# Template.net
KiCad netlist of a schematic drawn in Altium Designer
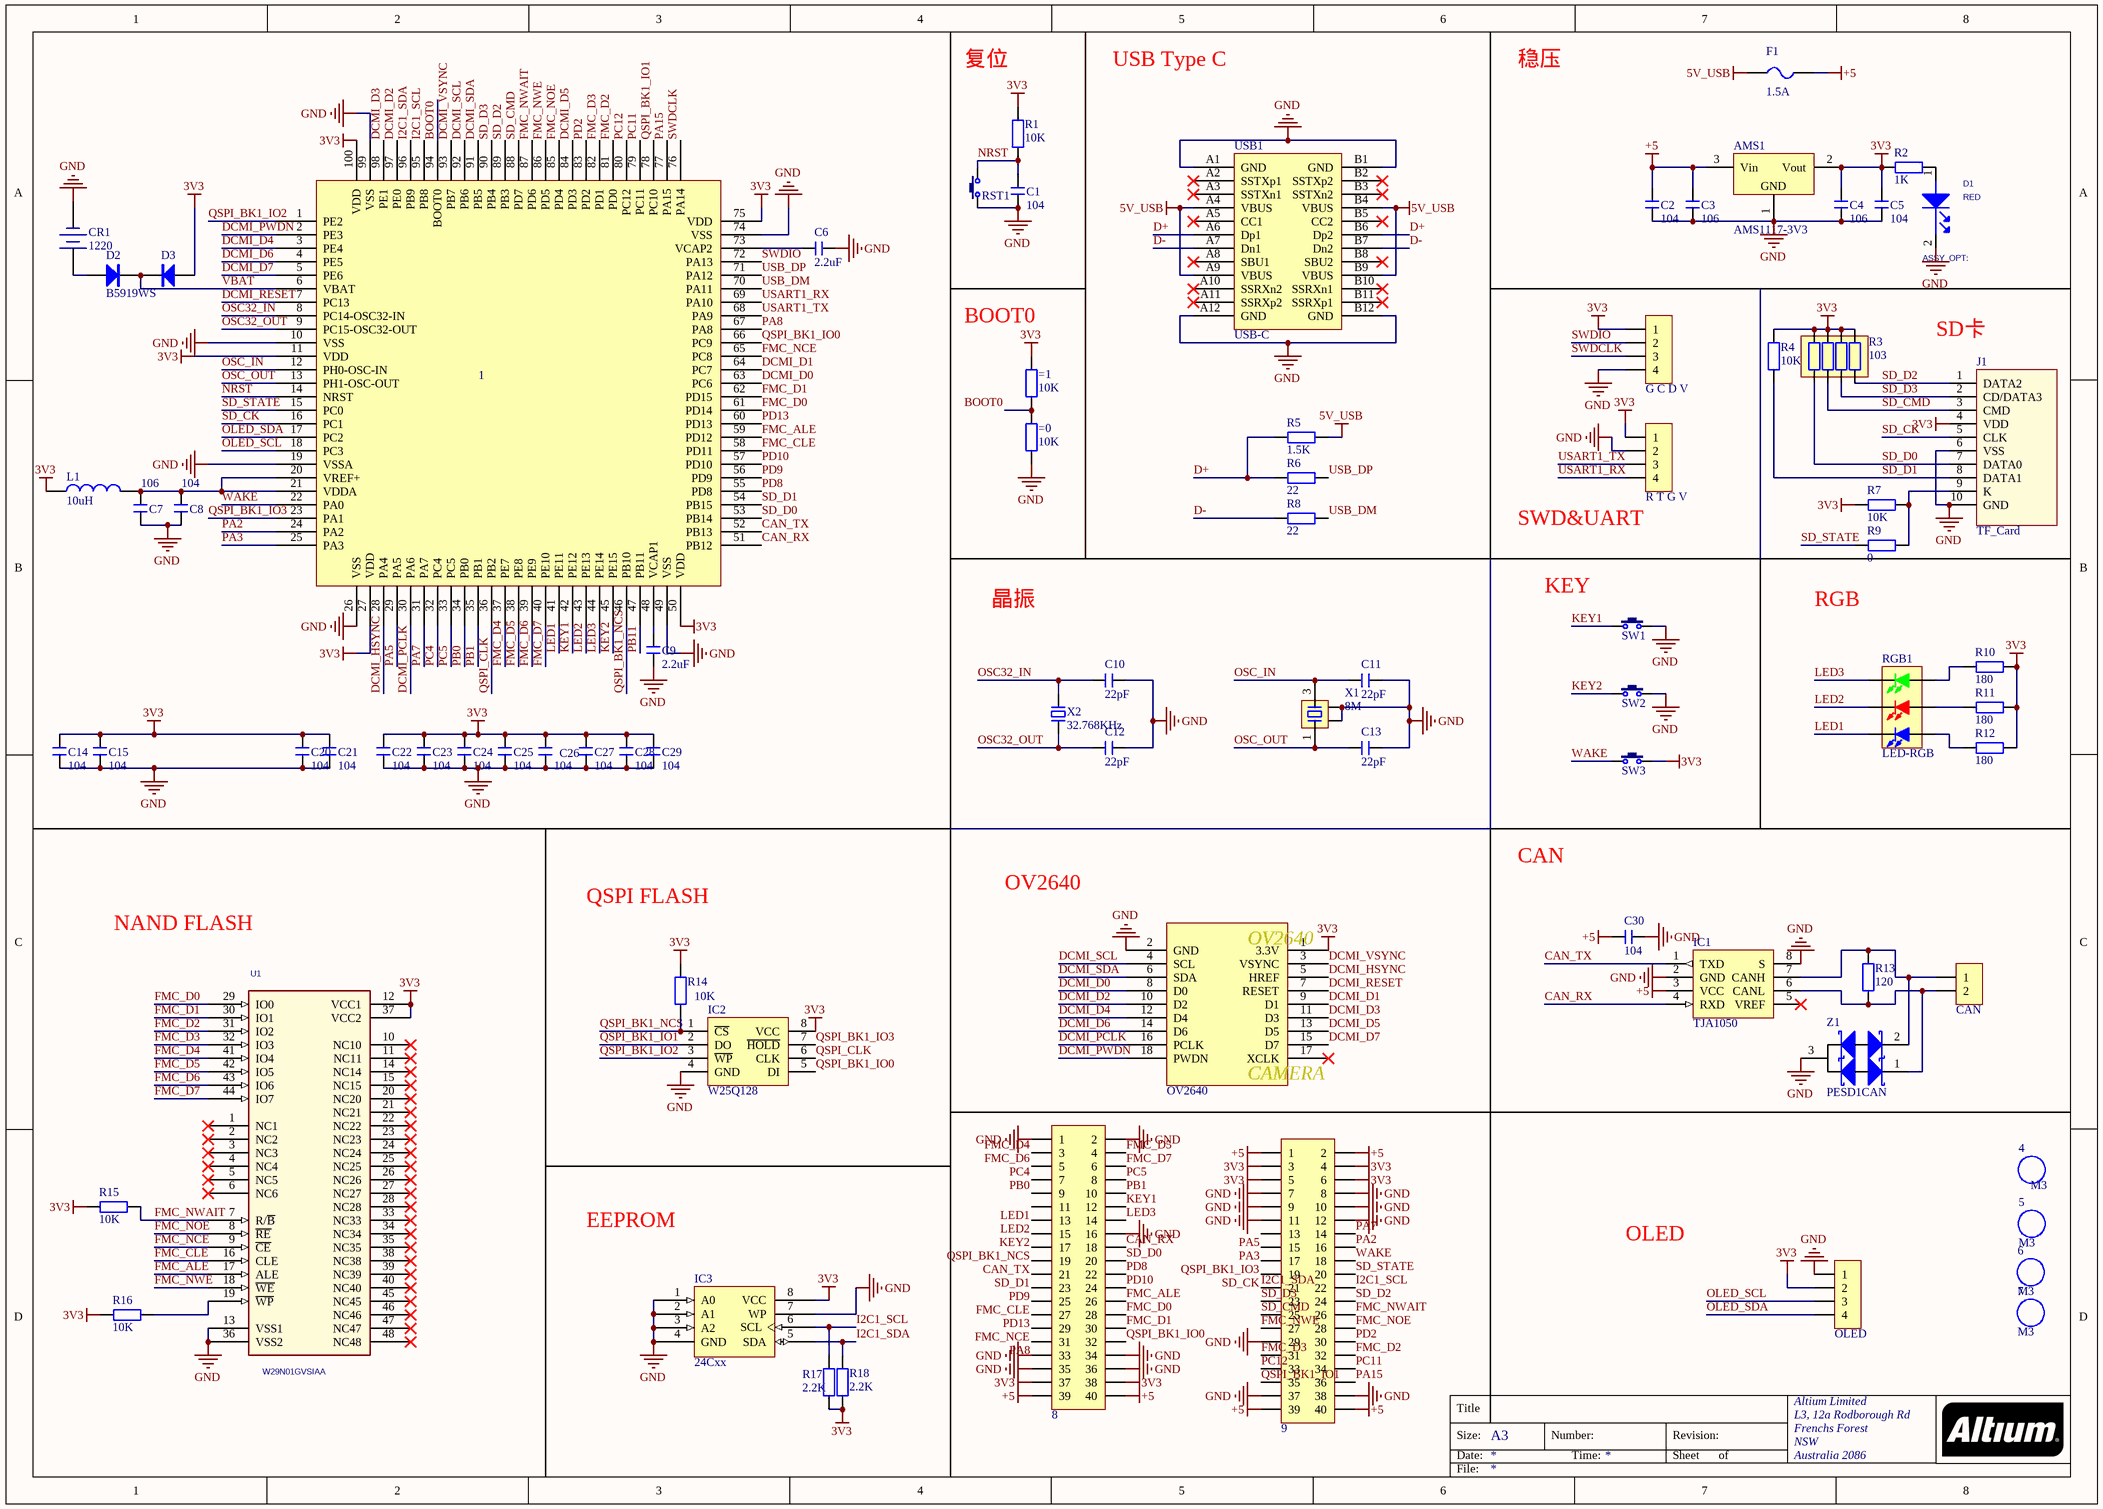
[diagram p0: Template.SchDoc]

(export (version "E")
  (design (tool "Eeschema 10.0.6"))
  (components
    (comp (ref "1")
      (value "~")
      (footprint "LQFP100 14x14_M")
      (libsource (lib "野火_H750X_核心板_V1.0_原理图封装库_AD格式") (part "stm32h750vbt6"))
    )
    (comp (ref "4")
      (value "M3")
      (footprint "M3 125X200")
      (description "铜柱孔")
      (fields (field (name "版权归属") "源创客"))
      (libsource (lib "15.1 - 未分类器件") (part "M3"))
    )
    (comp (ref "5")
      (value "M3")
      (footprint "M3 125X200")
      (description "铜柱孔")
      (fields (field (name "版权归属") "源创客"))
      (libsource (lib "15.1 - 未分类器件") (part "M3"))
    )
    (comp (ref "6")
      (value "M3")
      (footprint "M3 125X200")
      (description "铜柱孔")
      (fields (field (name "版权归属") "源创客"))
      (libsource (lib "15.1 - 未分类器件") (part "M3"))
    )
    (comp (ref "7")
      (value "M3")
      (footprint "M3 125X200")
      (description "铜柱孔")
      (fields (field (name "版权归属") "源创客"))
      (libsource (lib "15.1 - 未分类器件") (part "M3"))
    )
    (comp (ref "8")
      (value "Header 2X11")
      (footprint "HDR2.54-LI-2x20P")
      (description "20*2P接插件")
      (fields (field (name "版权归属") "源创客"))
      (libsource (lib "4.5   - 接插件-脚距2.54") (part "Header 20X2"))
    )
    (comp (ref "9")
      (value "Header 2X11")
      (footprint "HDR2.54-LI-2x20P")
      (description "20*2P接插件")
      (fields (field (name "版权归属") "源创客"))
      (libsource (lib "4.5   - 接插件-脚距2.54") (part "Header 20X2"))
    )
    (comp (ref "=0")
      (value "10K")
      (footprint "R 0603_L")
      (description "贴片电阻")
      (fields (field (name "版权归属") "源创客"))
      (libsource (lib "3.1   - 电阻-电容-电感") (part "R"))
    )
    (comp (ref "=1")
      (value "10K")
      (footprint "R 0603_L")
      (description "贴片电阻")
      (fields (field (name "版权归属") "源创客"))
      (libsource (lib "3.1   - 电阻-电容-电感") (part "R"))
    )
    (comp (ref "AMS1")
      (value "AMS1117-3V3")
      (footprint "SOT223_N")
      (description "三端稳压芯片")
      (fields (field (name "版权归属") "源创客"))
      (libsource (lib "1.3   - 电源类芯片") (part "AMS1117"))
    )
    (comp (ref "C1")
      (value "104")
      (footprint "C 0603_L")
      (description "无极性贴片电容")
      (fields (field (name "版权归属") "源创客"))
      (libsource (lib "3.1   - 电阻-电容-电感") (part "C"))
    )
    (comp (ref "C2")
      (value "104")
      (footprint "C 0603_L")
      (description "无极性贴片电容")
      (fields (field (name "版权归属") "源创客"))
      (libsource (lib "3.1   - 电阻-电容-电感") (part "C"))
    )
    (comp (ref "C3")
      (value "106")
      (footprint "C 0805_M")
      (description "无极性贴片电容")
      (fields (field (name "版权归属") "源创客"))
      (libsource (lib "3.1   - 电阻-电容-电感") (part "C"))
    )
    (comp (ref "C4")
      (value "106")
      (footprint "C 0805_M")
      (description "无极性贴片电容")
      (fields (field (name "版权归属") "源创客"))
      (libsource (lib "3.1   - 电阻-电容-电感") (part "C"))
    )
    (comp (ref "C5")
      (value "104")
      (footprint "C 0603_L")
      (description "无极性贴片电容")
      (fields (field (name "版权归属") "源创客"))
      (libsource (lib "3.1   - 电阻-电容-电感") (part "C"))
    )
    (comp (ref "C6")
      (value "2.2uF")
      (footprint "C 0603_L")
      (description "无极性贴片电容")
      (fields (field (name "版权归属") "源创客"))
      (libsource (lib "3.1   - 电阻-电容-电感") (part "C"))
    )
    (comp (ref "C7")
      (value "106")
      (footprint "C 0805_M")
      (description "无极性贴片电容")
      (fields (field (name "版权归属") "源创客"))
      (libsource (lib "3.1   - 电阻-电容-电感") (part "C"))
    )
    (comp (ref "C8")
      (value "104")
      (footprint "C 0603_L")
      (description "无极性贴片电容")
      (fields (field (name "版权归属") "源创客"))
      (libsource (lib "3.1   - 电阻-电容-电感") (part "C"))
    )
    (comp (ref "C9")
      (value "2.2uF")
      (footprint "C 0603_L")
      (description "无极性贴片电容")
      (fields (field (name "版权归属") "源创客"))
      (libsource (lib "3.1   - 电阻-电容-电感") (part "C"))
    )
    (comp (ref "C10")
      (value "22pF")
      (footprint "C 0603_L")
      (description "无极性贴片电容")
      (fields (field (name "版权归属") "源创客"))
      (libsource (lib "3.1   - 电阻-电容-电感") (part "C"))
    )
    (comp (ref "C11")
      (value "22pF")
      (footprint "C 0603_L")
      (description "无极性贴片电容")
      (fields (field (name "版权归属") "源创客"))
      (libsource (lib "3.1   - 电阻-电容-电感") (part "C"))
    )
    (comp (ref "C12")
      (value "22pF")
      (footprint "C 0603_L")
      (description "无极性贴片电容")
      (fields (field (name "版权归属") "源创客"))
      (libsource (lib "3.1   - 电阻-电容-电感") (part "C"))
    )
    (comp (ref "C13")
      (value "22pF")
      (footprint "C 0603_L")
      (description "无极性贴片电容")
      (fields (field (name "版权归属") "源创客"))
      (libsource (lib "3.1   - 电阻-电容-电感") (part "C"))
    )
    (comp (ref "C14")
      (value "104")
      (footprint "C 0603_L")
      (description "无极性贴片电容")
      (fields (field (name "版权归属") "源创客"))
      (libsource (lib "3.1   - 电阻-电容-电感") (part "C"))
    )
    (comp (ref "C15")
      (value "104")
      (footprint "C 0603_L")
      (description "无极性贴片电容")
      (fields (field (name "版权归属") "源创客"))
      (libsource (lib "3.1   - 电阻-电容-电感") (part "C"))
    )
    (comp (ref "C20")
      (value "104")
      (footprint "C 0603_L")
      (description "无极性贴片电容")
      (fields (field (name "版权归属") "源创客"))
      (libsource (lib "3.1   - 电阻-电容-电感") (part "C"))
    )
    (comp (ref "C21")
      (value "104")
      (footprint "C 0603_L")
      (description "无极性贴片电容")
      (fields (field (name "版权归属") "源创客"))
      (libsource (lib "3.1   - 电阻-电容-电感") (part "C"))
    )
    (comp (ref "C22")
      (value "104")
      (footprint "C 0603_L")
      (description "无极性贴片电容")
      (fields (field (name "版权归属") "源创客"))
      (libsource (lib "3.1   - 电阻-电容-电感") (part "C"))
    )
    (comp (ref "C23")
      (value "104")
      (footprint "C 0603_L")
      (description "无极性贴片电容")
      (fields (field (name "版权归属") "源创客"))
      (libsource (lib "3.1   - 电阻-电容-电感") (part "C"))
    )
    (comp (ref "C24")
      (value "104")
      (footprint "C 0603_L")
      (description "无极性贴片电容")
      (fields (field (name "版权归属") "源创客"))
      (libsource (lib "3.1   - 电阻-电容-电感") (part "C"))
    )
    (comp (ref "C25")
      (value "104")
      (footprint "C 0603_L")
      (description "无极性贴片电容")
      (fields (field (name "版权归属") "源创客"))
      (libsource (lib "3.1   - 电阻-电容-电感") (part "C"))
    )
    (comp (ref "C26")
      (value "104")
      (footprint "C 0603_L")
      (description "无极性贴片电容")
      (fields (field (name "版权归属") "源创客"))
      (libsource (lib "3.1   - 电阻-电容-电感") (part "C"))
    )
    (comp (ref "C27")
      (value "104")
      (footprint "C 0603_L")
      (description "无极性贴片电容")
      (fields (field (name "版权归属") "源创客"))
      (libsource (lib "3.1   - 电阻-电容-电感") (part "C"))
    )
    (comp (ref "C28")
      (value "104")
      (footprint "C 0603_L")
      (description "无极性贴片电容")
      (fields (field (name "版权归属") "源创客"))
      (libsource (lib "3.1   - 电阻-电容-电感") (part "C"))
    )
    (comp (ref "C29")
      (value "104")
      (footprint "C 0603_L")
      (description "无极性贴片电容")
      (fields (field (name "版权归属") "源创客"))
      (libsource (lib "3.1   - 电阻-电容-电感") (part "C"))
    )
    (comp (ref "C30")
      (value "104")
      (footprint "C 0603_L")
      (description "无极性贴片电容")
      (fields (field (name "版权归属") "源创客"))
      (libsource (lib "3.1   - 电阻-电容-电感") (part "C"))
    )
    (comp (ref "CAN")
      (value "HDR-1X2")
      (footprint "KF301-5.0-2P")
      (description "2P接插件")
      (fields (field (name "版权归属") "源创客"))
      (libsource (lib "4.9   - 接插件-脚距5.0") (part "Header 2"))
    )
    (comp (ref "CR1")
      (value "1220")
      (footprint "CR1220_A")
      (description "微型电池")
      (fields (field (name "版权归属") "源创客"))
      (libsource (lib "15.1 - 未分类器件") (part "CR-3V"))
    )
    (comp (ref "D1")
      (value "RED")
      (footprint "LED0603")
      (description "LED GRN SGL 25MA 0603")
      (libsource (lib "野火_H750X_核心板_V1.0_原理图封装库_AD格式") (part "LED_0"))
    )
    (comp (ref "D2")
      (value "B5919WS")
      (footprint "SOD-323")
      (description "肖特基二极管")
      (fields (field (name "版权归属") "源创客"))
      (libsource (lib "8.1   - 二极管-整流桥") (part "1N5819"))
    )
    (comp (ref "D3")
      (value "~")
      (footprint "SOD-323")
      (description "肖特基二极管")
      (fields (field (name "版权归属") "源创客"))
      (libsource (lib "8.1   - 二极管-整流桥") (part "1N5819"))
    )
    (comp (ref "F1")
      (value "1.5A")
      (footprint "FU 1812")
      (description "贴片保险丝")
      (fields (field (name "版权归属") "源创客"))
      (libsource (lib "10.1 - 保险丝-晶振") (part "FU"))
    )
    (comp (ref "G C D V")
      (value "HDR-1X4")
      (footprint "HDR2.54-WI-4P")
      (description "4P接插件")
      (fields (field (name "版权归属") "源创客"))
      (libsource (lib "4.5   - 接插件-脚距2.54") (part "Header 4"))
    )
    (comp (ref "IC1")
      (value "TJA1050")
      (footprint "SOP8_N")
      (description "CAN总线收发芯片")
      (fields (field (name "版权归属") "源创客"))
      (libsource (lib "1.1   - IC芯片") (part "TJA1050"))
    )
    (comp (ref "IC2")
      (value "W25Q128")
      (footprint "SOP8W_N")
      (description "外置Flash")
      (fields (field (name "版权归属") "源创客"))
      (libsource (lib "1.1   - IC芯片") (part "W25Qxx"))
    )
    (comp (ref "IC3")
      (value "24Cxx")
      (footprint "SOP8_L")
      (description "外置EEPROM")
      (fields (field (name "版权归属") "源创客"))
      (libsource (lib "1.1   - IC芯片") (part "24Cxx"))
    )
    (comp (ref "J1")
      (value "TF_Card")
      (footprint "Micro SD")
      (description "TF卡座")
      (fields (field (name "版权归属") "源创客"))
      (libsource (lib "4.1   - 接口类") (part "TF_Card"))
    )
    (comp (ref "L1")
      (value "10uH")
      (footprint "L 0805")
      (description "小功率贴片电感")
      (fields (field (name "版权归属") "源创客"))
      (libsource (lib "3.1   - 电阻-电容-电感") (part "L"))
    )
    (comp (ref "OLED")
      (value "OLED")
      (footprint "HDR2.54-M-LI-4P")
      (description "4P接插件")
      (fields (field (name "版权归属") "源创客"))
      (libsource (lib "4.5   - 接插件-脚距2.54") (part "Header 4"))
    )
    (comp (ref "OV2640")
      (value "OV2640")
      (footprint "OV2640")
      (description "摄像头")
      (libsource (lib "张方林_Library") (part "OV2640"))
    )
    (comp (ref "R T G V")
      (value "HDR-1X4")
      (footprint "HDR2.54-LI-4P")
      (description "4P接插件")
      (fields (field (name "版权归属") "源创客"))
      (libsource (lib "4.5   - 接插件-脚距2.54") (part "Header 4"))
    )
    (comp (ref "R1")
      (value "10K")
      (footprint "R 0603_L")
      (description "贴片电阻")
      (fields (field (name "版权归属") "源创客"))
      (libsource (lib "3.1   - 电阻-电容-电感") (part "R"))
    )
    (comp (ref "R2")
      (value "1K")
      (footprint "R 0603_L")
      (description "贴片电阻")
      (fields (field (name "版权归属") "源创客"))
      (libsource (lib "3.1   - 电阻-电容-电感") (part "R"))
    )
    (comp (ref "R3")
      (value "103")
      (footprint "RCA-8P4R-0603")
      (description "贴片网络排阻")
      (fields (field (name "版权归属") "源创客"))
      (libsource (lib "3.1   - 电阻-电容-电感") (part "R-8P4R"))
    )
    (comp (ref "R4")
      (value "10K")
      (footprint "R 0603_L")
      (description "贴片电阻")
      (fields (field (name "版权归属") "源创客"))
      (libsource (lib "3.1   - 电阻-电容-电感") (part "R"))
    )
    (comp (ref "R5")
      (value "1.5K")
      (footprint "R 0603_L")
      (description "贴片电阻")
      (fields (field (name "版权归属") "源创客"))
      (libsource (lib "3.1   - 电阻-电容-电感") (part "R"))
    )
    (comp (ref "R6")
      (value "22")
      (footprint "R 0603_L")
      (description "贴片电阻")
      (fields (field (name "版权归属") "源创客"))
      (libsource (lib "3.1   - 电阻-电容-电感") (part "R"))
    )
    (comp (ref "R7")
      (value "10K")
      (footprint "R 0603_L")
      (description "贴片电阻")
      (fields (field (name "版权归属") "源创客"))
      (libsource (lib "3.1   - 电阻-电容-电感") (part "R"))
    )
    (comp (ref "R8")
      (value "22")
      (footprint "R 0603_L")
      (description "贴片电阻")
      (fields (field (name "版权归属") "源创客"))
      (libsource (lib "3.1   - 电阻-电容-电感") (part "R"))
    )
    (comp (ref "R9")
      (value "0")
      (footprint "R 0603_L")
      (description "贴片电阻")
      (fields (field (name "版权归属") "源创客"))
      (libsource (lib "3.1   - 电阻-电容-电感") (part "R"))
    )
    (comp (ref "R10")
      (value "180")
      (footprint "R 0603_L")
      (description "贴片电阻")
      (fields (field (name "版权归属") "源创客"))
      (libsource (lib "3.1   - 电阻-电容-电感") (part "R"))
    )
    (comp (ref "R11")
      (value "180")
      (footprint "R 0603_L")
      (description "贴片电阻")
      (fields (field (name "版权归属") "源创客"))
      (libsource (lib "3.1   - 电阻-电容-电感") (part "R"))
    )
    (comp (ref "R12")
      (value "180")
      (footprint "R 0603_L")
      (description "贴片电阻")
      (fields (field (name "版权归属") "源创客"))
      (libsource (lib "3.1   - 电阻-电容-电感") (part "R"))
    )
    (comp (ref "R13")
      (value "120")
      (footprint "R 0603_L")
      (description "贴片电阻")
      (fields (field (name "版权归属") "源创客"))
      (libsource (lib "3.1   - 电阻-电容-电感") (part "R"))
    )
    (comp (ref "R14")
      (value "10K")
      (footprint "R 0603_L")
      (description "贴片电阻")
      (fields (field (name "版权归属") "源创客"))
      (libsource (lib "3.1   - 电阻-电容-电感") (part "R"))
    )
    (comp (ref "R15")
      (value "10K")
      (footprint "R 0603_L")
      (description "贴片电阻")
      (fields (field (name "版权归属") "源创客"))
      (libsource (lib "3.1   - 电阻-电容-电感") (part "R"))
    )
    (comp (ref "R16")
      (value "10K")
      (footprint "R 0603_L")
      (description "贴片电阻")
      (fields (field (name "版权归属") "源创客"))
      (libsource (lib "3.1   - 电阻-电容-电感") (part "R"))
    )
    (comp (ref "R17")
      (value "2.2K")
      (footprint "R 0603_L")
      (description "贴片电阻")
      (fields (field (name "版权归属") "源创客"))
      (libsource (lib "3.1   - 电阻-电容-电感") (part "R"))
    )
    (comp (ref "R18")
      (value "2.2K")
      (footprint "R 0603_L")
      (description "贴片电阻")
      (fields (field (name "版权归属") "源创客"))
      (libsource (lib "3.1   - 电阻-电容-电感") (part "R"))
    )
    (comp (ref "RGB1")
      (value "LED-RGB")
      (footprint "LED 5050")
      (description "三基色LED")
      (fields (field (name "版权归属") "源创客"))
      (libsource (lib "9.1   - LED") (part "LED-RGB"))
    )
    (comp (ref "RST1")
      (value "3x6x5")
      (footprint "TSW SMD-3*6*2.5")
      (description "3x6轻触开关")
      (fields (field (name "版权归属") "源创客"))
      (libsource (lib "5.1   - 按键-开关") (part "TSW 3x6"))
    )
    (comp (ref "SW1")
      (value "3x6x5")
      (footprint "TSW SMD-3*6*2.5")
      (description "3x6轻触开关")
      (fields (field (name "版权归属") "源创客"))
      (libsource (lib "") (part "TSW 3x6_1"))
    )
    (comp (ref "SW2")
      (value "3x6x5")
      (footprint "TSW SMD-3*6*2.5")
      (description "3x6轻触开关")
      (fields (field (name "版权归属") "源创客"))
      (libsource (lib "") (part "TSW 3x6_1"))
    )
    (comp (ref "SW3")
      (value "3x6x5")
      (footprint "TSW SMD-3*6*2.5")
      (description "3x6轻触开关")
      (fields (field (name "版权归属") "源创客"))
      (libsource (lib "") (part "TSW 3x6_1"))
    )
    (comp (ref "U1")
      (value "W29N01GVSIAA")
      (footprint "TSOP48")
      (description "IC MEM SDRAM 16MX16 6NS 3.3V VFBGA54")
      (libsource (lib "野火_H750X_核心板_V1.0_原理图封装库_AD格式") (part "W29N01GVSIAA"))
    )
    (comp (ref "USB1")
      (value "USB-C")
      (footprint "USB-C/S_A")
      (description "USB-C型母接口")
      (fields (field (name "版权归属") "源创客"))
      (libsource (lib "4.1   - 接口类") (part "USB-C/S"))
    )
    (comp (ref "X1")
      (value "8M")
      (footprint "OSC 5032-4P")
      (description "4脚无源晶振")
      (fields (field (name "版权归属") "源创客"))
      (libsource (lib "10.1 - 保险丝-晶振") (part "XTAL-4P"))
    )
    (comp (ref "X2")
      (value "32.768KHz")
      (footprint "OSC-2x6-WI-B")
      (description "2脚无源脚晶振")
      (fields (field (name "版权归属") "源创客"))
      (libsource (lib "10.1 - 保险丝-晶振") (part "XTAL-2P"))
    )
    (comp (ref "Z1")
      (value "PESD1CAN")
      (footprint "SOT23-3")
      (description "过压保护")
      (libsource (lib "张方林_Library") (part "PESD1CAN"))
    )
  )
  (nets
    (net (code "1") (name "+5") (class "Default")
      (node (ref "8") (pin "39") (pinfunction "39_39") (pintype "passive"))
      (node (ref "8") (pin "40") (pinfunction "40_40") (pintype "passive"))
      (node (ref "9") (pin "1") (pinfunction "1_1") (pintype "passive"))
      (node (ref "9") (pin "2") (pinfunction "2_2") (pintype "passive"))
      (node (ref "9") (pin "39") (pinfunction "39_39") (pintype "passive"))
      (node (ref "9") (pin "40") (pinfunction "40_40") (pintype "passive"))
      (node (ref "AMS1") (pin "3") (pinfunction "Vin_3") (pintype "passive"))
      (node (ref "C2") (pin "2") (pinfunction "2_2") (pintype "passive"))
      (node (ref "C3") (pin "2") (pinfunction "2_2") (pintype "passive"))
      (node (ref "C30") (pin "1") (pinfunction "1_1") (pintype "passive"))
      (node (ref "F1") (pin "2") (pinfunction "2_2") (pintype "passive"))
      (node (ref "IC1") (pin "3") (pinfunction "VCC_3") (pintype "passive"))
    )
    (net (code "2") (name "/BOOT0") (class "Default")
      (node (ref "1") (pin "94") (pinfunction "BOOT0_94") (pintype "passive"))
      (node (ref "=0") (pin "1") (pinfunction "1_1") (pintype "passive"))
      (node (ref "=1") (pin "2") (pinfunction "2_2") (pintype "passive"))
    )
    (net (code "3") (name "/CAN_RX") (class "Default")
      (node (ref "1") (pin "51") (pinfunction "PB12_51") (pintype "passive"))
      (node (ref "8") (pin "18") (pinfunction "18_18") (pintype "passive"))
      (node (ref "IC1") (pin "4") (pinfunction "RXD_4") (pintype "input"))
    )
    (net (code "4") (name "/CAN_TX") (class "Default")
      (node (ref "1") (pin "52") (pinfunction "PB13_52") (pintype "passive"))
      (node (ref "8") (pin "19") (pinfunction "19_19") (pintype "passive"))
      (node (ref "IC1") (pin "1") (pinfunction "TXD_1") (pintype "output"))
    )
    (net (code "5") (name "/D+") (class "Default")
      (node (ref "R5") (pin "1") (pinfunction "1_1") (pintype "passive"))
      (node (ref "R6") (pin "2") (pinfunction "2_2") (pintype "passive"))
      (node (ref "USB1") (pin "A6") (pinfunction "Dp1_A6") (pintype "passive"))
      (node (ref "USB1") (pin "B6") (pinfunction "Dp2_B6") (pintype "passive"))
    )
    (net (code "6") (name "/D-") (class "Default")
      (node (ref "R8") (pin "2") (pinfunction "2_2") (pintype "passive"))
      (node (ref "USB1") (pin "A7") (pinfunction "Dn1_A7") (pintype "passive"))
      (node (ref "USB1") (pin "B7") (pinfunction "Dn2_B7") (pintype "passive"))
    )
    (net (code "7") (name "/DCMI_D0") (class "Default")
      (node (ref "1") (pin "63") (pinfunction "PC6_63") (pintype "passive"))
      (node (ref "OV2640") (pin "8") (pinfunction "D0_8") (pintype "passive"))
    )
    (net (code "8") (name "/DCMI_D1") (class "Default")
      (node (ref "1") (pin "64") (pinfunction "PC7_64") (pintype "passive"))
      (node (ref "OV2640") (pin "9") (pinfunction "D1_9") (pintype "passive"))
    )
    (net (code "9") (name "/DCMI_D2") (class "Default")
      (node (ref "1") (pin "97") (pinfunction "PE0_97") (pintype "passive"))
      (node (ref "OV2640") (pin "10") (pinfunction "D2_10") (pintype "passive"))
    )
    (net (code "10") (name "/DCMI_D3") (class "Default")
      (node (ref "1") (pin "98") (pinfunction "PE1_98") (pintype "passive"))
      (node (ref "OV2640") (pin "11") (pinfunction "D3_11") (pintype "passive"))
    )
    (net (code "11") (name "/DCMI_D4") (class "Default")
      (node (ref "1") (pin "3") (pinfunction "PE4_3") (pintype "passive"))
      (node (ref "OV2640") (pin "12") (pinfunction "D4_12") (pintype "passive"))
    )
    (net (code "12") (name "/DCMI_D5") (class "Default")
      (node (ref "1") (pin "84") (pinfunction "PD3_84") (pintype "passive"))
      (node (ref "OV2640") (pin "13") (pinfunction "D5_13") (pintype "passive"))
    )
    (net (code "13") (name "/DCMI_D6") (class "Default")
      (node (ref "1") (pin "4") (pinfunction "PE5_4") (pintype "passive"))
      (node (ref "OV2640") (pin "14") (pinfunction "D6_14") (pintype "passive"))
    )
    (net (code "14") (name "/DCMI_D7") (class "Default")
      (node (ref "1") (pin "5") (pinfunction "PE6_5") (pintype "passive"))
      (node (ref "OV2640") (pin "15") (pinfunction "D7_15") (pintype "passive"))
    )
    (net (code "15") (name "/DCMI_HSYNC") (class "Default")
      (node (ref "1") (pin "28") (pinfunction "PA4_28") (pintype "passive"))
      (node (ref "OV2640") (pin "5") (pinfunction "HREF_5") (pintype "passive"))
    )
    (net (code "16") (name "/DCMI_PCLK") (class "Default")
      (node (ref "1") (pin "30") (pinfunction "PA6_30") (pintype "passive"))
      (node (ref "OV2640") (pin "16") (pinfunction "PCLK_16") (pintype "passive"))
    )
    (net (code "17") (name "/DCMI_PWDN") (class "Default")
      (node (ref "1") (pin "2") (pinfunction "PE3_2") (pintype "passive"))
      (node (ref "OV2640") (pin "18") (pinfunction "PWDN_18") (pintype "passive"))
    )
    (net (code "18") (name "/DCMI_RESET") (class "Default")
      (node (ref "1") (pin "7") (pinfunction "PC13_7") (pintype "passive"))
      (node (ref "OV2640") (pin "7") (pinfunction "RESET_7") (pintype "passive"))
    )
    (net (code "19") (name "/DCMI_SCL") (class "Default")
      (node (ref "1") (pin "92") (pinfunction "PB6_92") (pintype "passive"))
      (node (ref "OV2640") (pin "4") (pinfunction "SCL_4") (pintype "passive"))
    )
    (net (code "20") (name "/DCMI_SDA") (class "Default")
      (node (ref "1") (pin "91") (pinfunction "PB5_91") (pintype "passive"))
      (node (ref "OV2640") (pin "6") (pinfunction "SDA_6") (pintype "passive"))
    )
    (net (code "21") (name "/DCMI_VSYNC") (class "Default")
      (node (ref "1") (pin "93") (pinfunction "PB7_93") (pintype "passive"))
      (node (ref "OV2640") (pin "3") (pinfunction "VSYNC_3") (pintype "passive"))
    )
    (net (code "22") (name "/FMC_ALE") (class "Default")
      (node (ref "1") (pin "59") (pinfunction "PD12_59") (pintype "passive"))
      (node (ref "8") (pin "26") (pinfunction "26_26") (pintype "passive"))
      (node (ref "U1") (pin "17") (pinfunction "ALE_17") (pintype "input"))
    )
    (net (code "23") (name "/FMC_CLE") (class "Default")
      (node (ref "1") (pin "58") (pinfunction "PD11_58") (pintype "passive"))
      (node (ref "8") (pin "25") (pinfunction "25_25") (pintype "passive"))
      (node (ref "U1") (pin "16") (pinfunction "CLE_16") (pintype "input"))
    )
    (net (code "24") (name "/FMC_D0") (class "Default")
      (node (ref "1") (pin "61") (pinfunction "PD14_61") (pintype "passive"))
      (node (ref "8") (pin "28") (pinfunction "28_28") (pintype "passive"))
      (node (ref "U1") (pin "29") (pinfunction "IO0_29") (pintype "input"))
    )
    (net (code "25") (name "/FMC_D1") (class "Default")
      (node (ref "1") (pin "62") (pinfunction "PD15_62") (pintype "passive"))
      (node (ref "8") (pin "30") (pinfunction "30_30") (pintype "passive"))
      (node (ref "U1") (pin "30") (pinfunction "IO1_30") (pintype "input"))
    )
    (net (code "26") (name "/FMC_D2") (class "Default")
      (node (ref "1") (pin "81") (pinfunction "PD0_81") (pintype "passive"))
      (node (ref "9") (pin "32") (pinfunction "32_32") (pintype "passive"))
      (node (ref "U1") (pin "31") (pinfunction "IO2_31") (pintype "input"))
    )
    (net (code "27") (name "/FMC_D3") (class "Default")
      (node (ref "1") (pin "82") (pinfunction "PD1_82") (pintype "passive"))
      (node (ref "9") (pin "31") (pinfunction "31_31") (pintype "passive"))
      (node (ref "U1") (pin "32") (pinfunction "IO3_32") (pintype "input"))
    )
    (net (code "28") (name "/FMC_D4") (class "Default")
      (node (ref "1") (pin "37") (pinfunction "PE7_37") (pintype "passive"))
      (node (ref "8") (pin "3") (pinfunction "3_3") (pintype "passive"))
      (node (ref "U1") (pin "41") (pinfunction "IO4_41") (pintype "input"))
    )
    (net (code "29") (name "/FMC_D5") (class "Default")
      (node (ref "1") (pin "38") (pinfunction "PE8_38") (pintype "passive"))
      (node (ref "8") (pin "4") (pinfunction "4_4") (pintype "passive"))
      (node (ref "U1") (pin "42") (pinfunction "IO5_42") (pintype "input"))
    )
    (net (code "30") (name "/FMC_D6") (class "Default")
      (node (ref "1") (pin "39") (pinfunction "PE9_39") (pintype "passive"))
      (node (ref "8") (pin "5") (pinfunction "5_5") (pintype "passive"))
      (node (ref "U1") (pin "43") (pinfunction "IO6_43") (pintype "input"))
    )
    (net (code "31") (name "/FMC_D7") (class "Default")
      (node (ref "1") (pin "40") (pinfunction "PE10_40") (pintype "passive"))
      (node (ref "8") (pin "6") (pinfunction "6_6") (pintype "passive"))
      (node (ref "U1") (pin "44") (pinfunction "IO7_44") (pintype "input"))
    )
    (net (code "32") (name "/FMC_NCE") (class "Default")
      (node (ref "1") (pin "65") (pinfunction "PC8_65") (pintype "passive"))
      (node (ref "8") (pin "29") (pinfunction "29_29") (pintype "passive"))
      (node (ref "U1") (pin "9") (pinfunction "~{CE}_9") (pintype "input"))
    )
    (net (code "33") (name "/FMC_NOE") (class "Default")
      (node (ref "1") (pin "85") (pinfunction "PD4_85") (pintype "passive"))
      (node (ref "9") (pin "28") (pinfunction "28_28") (pintype "passive"))
      (node (ref "U1") (pin "8") (pinfunction "~{RE}_8") (pintype "input"))
    )
    (net (code "34") (name "/FMC_NWAIT") (class "Default")
      (node (ref "1") (pin "87") (pinfunction "PD6_87") (pintype "passive"))
      (node (ref "9") (pin "26") (pinfunction "26_26") (pintype "passive"))
      (node (ref "R15") (pin "2") (pinfunction "2_2") (pintype "passive"))
      (node (ref "U1") (pin "7") (pinfunction "R/~{B}_7") (pintype "input"))
    )
    (net (code "35") (name "/FMC_NWE") (class "Default")
      (node (ref "1") (pin "86") (pinfunction "PD5_86") (pintype "passive"))
      (node (ref "9") (pin "27") (pinfunction "27_27") (pintype "passive"))
      (node (ref "U1") (pin "18") (pinfunction "~{WE}_18") (pintype "input"))
    )
    (net (code "36") (name "/I2C1_SCL") (class "Default")
      (node (ref "1") (pin "95") (pinfunction "PB8_95") (pintype "passive"))
      (node (ref "9") (pin "22") (pinfunction "22_22") (pintype "passive"))
      (node (ref "IC3") (pin "6") (pinfunction "SCL_6") (pintype "input"))
      (node (ref "R17") (pin "2") (pinfunction "2_2") (pintype "passive"))
    )
    (net (code "37") (name "/I2C1_SDA") (class "Default")
      (node (ref "1") (pin "96") (pinfunction "PB9_96") (pintype "passive"))
      (node (ref "9") (pin "21") (pinfunction "21_21") (pintype "passive"))
      (node (ref "IC3") (pin "5") (pinfunction "SDA_5") (pintype "bidirectional"))
      (node (ref "R18") (pin "1") (pinfunction "1_1") (pintype "passive"))
    )
    (net (code "38") (name "/KEY1") (class "Default")
      (node (ref "1") (pin "42") (pinfunction "PE12_42") (pintype "passive"))
      (node (ref "8") (pin "12") (pinfunction "12_12") (pintype "passive"))
      (node (ref "SW1") (pin "1") (pinfunction "1_1") (pintype "passive"))
    )
    (net (code "39") (name "/KEY2") (class "Default")
      (node (ref "1") (pin "45") (pinfunction "PE15_45") (pintype "passive"))
      (node (ref "8") (pin "15") (pinfunction "15_15") (pintype "passive"))
      (node (ref "SW2") (pin "1") (pinfunction "1_1") (pintype "passive"))
    )
    (net (code "40") (name "/LED1") (class "Default")
      (node (ref "1") (pin "41") (pinfunction "PE11_41") (pintype "passive"))
      (node (ref "8") (pin "11") (pinfunction "11_11") (pintype "passive"))
      (node (ref "RGB1") (pin "1") (pinfunction "BULE_K_1") (pintype "passive"))
    )
    (net (code "41") (name "/LED2") (class "Default")
      (node (ref "1") (pin "43") (pinfunction "PE13_43") (pintype "passive"))
      (node (ref "8") (pin "13") (pinfunction "13_13") (pintype "passive"))
      (node (ref "RGB1") (pin "3") (pinfunction "RED_K_3") (pintype "passive"))
    )
    (net (code "42") (name "/LED3") (class "Default")
      (node (ref "1") (pin "44") (pinfunction "PE14_44") (pintype "passive"))
      (node (ref "8") (pin "14") (pinfunction "14_14") (pintype "passive"))
      (node (ref "RGB1") (pin "5") (pinfunction "GREEN_K_5") (pintype "passive"))
    )
    (net (code "43") (name "/NRST") (class "Default")
      (node (ref "1") (pin "14") (pinfunction "NRST_14") (pintype "passive"))
      (node (ref "C1") (pin "2") (pinfunction "2_2") (pintype "passive"))
      (node (ref "R1") (pin "2") (pinfunction "2_2") (pintype "passive"))
      (node (ref "RST1") (pin "2") (pinfunction "2_2") (pintype "passive"))
    )
    (net (code "44") (name "/OLED_SCL") (class "Default")
      (node (ref "1") (pin "18") (pinfunction "PC3_18") (pintype "passive"))
      (node (ref "OLED") (pin "3") (pinfunction "3_3") (pintype "passive"))
    )
    (net (code "45") (name "/OLED_SDA") (class "Default")
      (node (ref "1") (pin "17") (pinfunction "PC2_17") (pintype "passive"))
      (node (ref "OLED") (pin "4") (pinfunction "4_4") (pintype "passive"))
    )
    (net (code "46") (name "/OSC32_IN") (class "Default")
      (node (ref "1") (pin "8") (pinfunction "PC14-OSC32-IN_8") (pintype "passive"))
      (node (ref "C10") (pin "2") (pinfunction "2_2") (pintype "passive"))
      (node (ref "X2") (pin "1") (pinfunction "1_1") (pintype "passive"))
    )
    (net (code "47") (name "/OSC32_OUT") (class "Default")
      (node (ref "1") (pin "9") (pinfunction "PC15-OSC32-OUT_9") (pintype "passive"))
      (node (ref "C12") (pin "2") (pinfunction "2_2") (pintype "passive"))
      (node (ref "X2") (pin "2") (pinfunction "2_2") (pintype "passive"))
    )
    (net (code "48") (name "/OSC_IN") (class "Default")
      (node (ref "1") (pin "12") (pinfunction "PH0-OSC-IN_12") (pintype "passive"))
      (node (ref "C11") (pin "2") (pinfunction "2_2") (pintype "passive"))
      (node (ref "X1") (pin "3") (pinfunction "3_3") (pintype "passive"))
    )
    (net (code "49") (name "/OSC_OUT") (class "Default")
      (node (ref "1") (pin "13") (pinfunction "PH1-OSC-OUT_13") (pintype "passive"))
      (node (ref "C13") (pin "2") (pinfunction "2_2") (pintype "passive"))
      (node (ref "X1") (pin "1") (pinfunction "1_1") (pintype "passive"))
    )
    (net (code "50") (name "/PA2") (class "Default")
      (node (ref "1") (pin "24") (pinfunction "PA2_24") (pintype "passive"))
      (node (ref "9") (pin "16") (pinfunction "16_16") (pintype "passive"))
    )
    (net (code "51") (name "/PA3") (class "Default")
      (node (ref "1") (pin "25") (pinfunction "PA3_25") (pintype "passive"))
      (node (ref "9") (pin "15") (pinfunction "15_15") (pintype "passive"))
    )
    (net (code "52") (name "/PA5") (class "Default")
      (node (ref "1") (pin "29") (pinfunction "PA5_29") (pintype "passive"))
      (node (ref "9") (pin "13") (pinfunction "13_13") (pintype "passive"))
    )
    (net (code "53") (name "/PA7") (class "Default")
      (node (ref "1") (pin "31") (pinfunction "PA7_31") (pintype "passive"))
      (node (ref "9") (pin "14") (pinfunction "14_14") (pintype "passive"))
    )
    (net (code "54") (name "/PA8") (class "Default")
      (node (ref "1") (pin "67") (pinfunction "PA8_67") (pintype "passive"))
      (node (ref "8") (pin "31") (pinfunction "31_31") (pintype "passive"))
    )
    (net (code "55") (name "/PA15") (class "Default")
      (node (ref "1") (pin "77") (pinfunction "PA15_77") (pintype "passive"))
      (node (ref "9") (pin "36") (pinfunction "36_36") (pintype "passive"))
    )
    (net (code "56") (name "/PB0") (class "Default")
      (node (ref "1") (pin "34") (pinfunction "PB0_34") (pintype "passive"))
      (node (ref "8") (pin "9") (pinfunction "9_9") (pintype "passive"))
    )
    (net (code "57") (name "/PB1") (class "Default")
      (node (ref "1") (pin "35") (pinfunction "PB1_35") (pintype "passive"))
      (node (ref "8") (pin "10") (pinfunction "10_10") (pintype "passive"))
    )
    (net (code "58") (name "/PB11") (class "Default")
      (node (ref "1") (pin "47") (pinfunction "PB11_47") (pintype "passive"))
    )
    (net (code "59") (name "/PC4") (class "Default")
      (node (ref "1") (pin "32") (pinfunction "PC4_32") (pintype "passive"))
      (node (ref "8") (pin "7") (pinfunction "7_7") (pintype "passive"))
    )
    (net (code "60") (name "/PC5") (class "Default")
      (node (ref "1") (pin "33") (pinfunction "PC5_33") (pintype "passive"))
      (node (ref "8") (pin "8") (pinfunction "8_8") (pintype "passive"))
    )
    (net (code "61") (name "/PC11") (class "Default")
      (node (ref "1") (pin "79") (pinfunction "PC11_79") (pintype "passive"))
      (node (ref "9") (pin "34") (pinfunction "34_34") (pintype "passive"))
    )
    (net (code "62") (name "/PC12") (class "Default")
      (node (ref "1") (pin "80") (pinfunction "PC12_80") (pintype "passive"))
      (node (ref "9") (pin "33") (pinfunction "33_33") (pintype "passive"))
    )
    (net (code "63") (name "/PD2") (class "Default")
      (node (ref "1") (pin "83") (pinfunction "PD2_83") (pintype "passive"))
      (node (ref "9") (pin "30") (pinfunction "30_30") (pintype "passive"))
    )
    (net (code "64") (name "/PD8") (class "Default")
      (node (ref "1") (pin "55") (pinfunction "PD8_55") (pintype "passive"))
      (node (ref "8") (pin "22") (pinfunction "22_22") (pintype "passive"))
    )
    (net (code "65") (name "/PD9") (class "Default")
      (node (ref "1") (pin "56") (pinfunction "PD9_56") (pintype "passive"))
      (node (ref "8") (pin "23") (pinfunction "23_23") (pintype "passive"))
    )
    (net (code "66") (name "/PD10") (class "Default")
      (node (ref "1") (pin "57") (pinfunction "PD10_57") (pintype "passive"))
      (node (ref "8") (pin "24") (pinfunction "24_24") (pintype "passive"))
    )
    (net (code "67") (name "/PD13") (class "Default")
      (node (ref "1") (pin "60") (pinfunction "PD13_60") (pintype "passive"))
      (node (ref "8") (pin "27") (pinfunction "27_27") (pintype "passive"))
    )
    (net (code "68") (name "/QSPI_BK1_IO0") (class "Default")
      (node (ref "1") (pin "66") (pinfunction "PC9_66") (pintype "passive"))
      (node (ref "8") (pin "32") (pinfunction "32_32") (pintype "passive"))
      (node (ref "IC2") (pin "5") (pinfunction "DI_5") (pintype "passive"))
    )
    (net (code "69") (name "/QSPI_BK1_IO1") (class "Default")
      (node (ref "1") (pin "78") (pinfunction "PC10_78") (pintype "passive"))
      (node (ref "9") (pin "35") (pinfunction "35_35") (pintype "passive"))
      (node (ref "IC2") (pin "2") (pinfunction "DO_2") (pintype "passive"))
    )
    (net (code "70") (name "/QSPI_BK1_IO2") (class "Default")
      (node (ref "1") (pin "1") (pinfunction "PE2_1") (pintype "passive"))
      (node (ref "IC2") (pin "3") (pinfunction "~{WP}_3") (pintype "passive"))
    )
    (net (code "71") (name "/QSPI_BK1_IO3") (class "Default")
      (node (ref "1") (pin "23") (pinfunction "PA1_23") (pintype "passive"))
      (node (ref "9") (pin "17") (pinfunction "17_17") (pintype "passive"))
      (node (ref "IC2") (pin "7") (pinfunction "~{HOLD}_7") (pintype "passive"))
    )
    (net (code "72") (name "/QSPI_BK1_NCS") (class "Default")
      (node (ref "1") (pin "46") (pinfunction "PB10_46") (pintype "passive"))
      (node (ref "8") (pin "17") (pinfunction "17_17") (pintype "passive"))
      (node (ref "IC2") (pin "1") (pinfunction "~{CS}_1") (pintype "passive"))
      (node (ref "R14") (pin "2") (pinfunction "2_2") (pintype "passive"))
    )
    (net (code "73") (name "/QSPI_CLK") (class "Default")
      (node (ref "1") (pin "36") (pinfunction "PB2_36") (pintype "passive"))
      (node (ref "IC2") (pin "6") (pinfunction "CLK_6") (pintype "passive"))
    )
    (net (code "74") (name "/SD_CK") (class "Default")
      (node (ref "1") (pin "16") (pinfunction "PC1_16") (pintype "passive"))
      (node (ref "9") (pin "19") (pinfunction "19_19") (pintype "passive"))
      (node (ref "J1") (pin "5") (pinfunction "CLK_5") (pintype "passive"))
    )
    (net (code "75") (name "/SD_CMD") (class "Default")
      (node (ref "1") (pin "88") (pinfunction "PD7_88") (pintype "passive"))
      (node (ref "9") (pin "25") (pinfunction "25_25") (pintype "passive"))
      (node (ref "J1") (pin "3") (pinfunction "CMD_3") (pintype "passive"))
      (node (ref "R3") (pin "2") (pinfunction "2_2") (pintype "passive"))
    )
    (net (code "76") (name "/SD_D0") (class "Default")
      (node (ref "1") (pin "53") (pinfunction "PB14_53") (pintype "passive"))
      (node (ref "8") (pin "20") (pinfunction "20_20") (pintype "passive"))
      (node (ref "J1") (pin "7") (pinfunction "DATA0_7") (pintype "passive"))
      (node (ref "R3") (pin "1") (pinfunction "1_1") (pintype "passive"))
    )
    (net (code "77") (name "/SD_D1") (class "Default")
      (node (ref "1") (pin "54") (pinfunction "PB15_54") (pintype "passive"))
      (node (ref "8") (pin "21") (pinfunction "21_21") (pintype "passive"))
      (node (ref "J1") (pin "8") (pinfunction "DATA1_8") (pintype "passive"))
      (node (ref "R4") (pin "1") (pinfunction "1_1") (pintype "passive"))
    )
    (net (code "78") (name "/SD_D2") (class "Default")
      (node (ref "1") (pin "89") (pinfunction "PB3_89") (pintype "passive"))
      (node (ref "9") (pin "24") (pinfunction "24_24") (pintype "passive"))
      (node (ref "J1") (pin "1") (pinfunction "DATA2_1") (pintype "passive"))
      (node (ref "R3") (pin "4") (pinfunction "4_4") (pintype "passive"))
    )
    (net (code "79") (name "/SD_D3") (class "Default")
      (node (ref "1") (pin "90") (pinfunction "PB4_90") (pintype "passive"))
      (node (ref "9") (pin "23") (pinfunction "23_23") (pintype "passive"))
      (node (ref "J1") (pin "2") (pinfunction "CD/DATA3_2") (pintype "passive"))
      (node (ref "R3") (pin "3") (pinfunction "3_3") (pintype "passive"))
    )
    (net (code "80") (name "/SD_STATE") (class "Default")
      (node (ref "1") (pin "15") (pinfunction "PC0_15") (pintype "passive"))
      (node (ref "9") (pin "20") (pinfunction "20_20") (pintype "passive"))
      (node (ref "R9") (pin "2") (pinfunction "2_2") (pintype "passive"))
    )
    (net (code "81") (name "/SWDCLK") (class "Default")
      (node (ref "1") (pin "76") (pinfunction "PA14_76") (pintype "passive"))
      (node (ref "G C D V") (pin "3") (pinfunction "3_3") (pintype "passive"))
    )
    (net (code "82") (name "/SWDIO") (class "Default")
      (node (ref "1") (pin "72") (pinfunction "PA13_72") (pintype "passive"))
      (node (ref "G C D V") (pin "2") (pinfunction "2_2") (pintype "passive"))
    )
    (net (code "83") (name "/USART1_RX") (class "Default")
      (node (ref "1") (pin "69") (pinfunction "PA10_69") (pintype "passive"))
      (node (ref "R T G V") (pin "4") (pinfunction "4_4") (pintype "passive"))
    )
    (net (code "84") (name "/USART1_TX") (class "Default")
      (node (ref "1") (pin "68") (pinfunction "PA9_68") (pintype "passive"))
      (node (ref "R T G V") (pin "3") (pinfunction "3_3") (pintype "passive"))
    )
    (net (code "85") (name "/USB_DM") (class "Default")
      (node (ref "1") (pin "70") (pinfunction "PA11_70") (pintype "passive"))
      (node (ref "R8") (pin "1") (pinfunction "1_1") (pintype "passive"))
    )
    (net (code "86") (name "/USB_DP") (class "Default")
      (node (ref "1") (pin "71") (pinfunction "PA12_71") (pintype "passive"))
      (node (ref "R6") (pin "1") (pinfunction "1_1") (pintype "passive"))
    )
    (net (code "87") (name "/VBAT") (class "Default")
      (node (ref "1") (pin "6") (pinfunction "VBAT_6") (pintype "passive"))
      (node (ref "D2") (pin "2") (pinfunction "K_2") (pintype "passive"))
      (node (ref "D3") (pin "2") (pinfunction "K_2") (pintype "passive"))
    )
    (net (code "88") (name "/WAKE") (class "Default")
      (node (ref "1") (pin "22") (pinfunction "PA0_22") (pintype "passive"))
      (node (ref "9") (pin "18") (pinfunction "18_18") (pintype "passive"))
      (node (ref "SW3") (pin "1") (pinfunction "1_1") (pintype "passive"))
    )
    (net (code "89") (name "3V3") (class "Default")
      (node (ref "1") (pin "100") (pinfunction "VDD_100") (pintype "passive"))
      (node (ref "1") (pin "11") (pinfunction "VDD_11") (pintype "passive"))
      (node (ref "1") (pin "27") (pinfunction "VDD_27") (pintype "passive"))
      (node (ref "1") (pin "50") (pinfunction "VDD_50") (pintype "passive"))
      (node (ref "1") (pin "75") (pinfunction "VDD_75") (pintype "passive"))
      (node (ref "8") (pin "37") (pinfunction "37_37") (pintype "passive"))
      (node (ref "8") (pin "38") (pinfunction "38_38") (pintype "passive"))
      (node (ref "9") (pin "3") (pinfunction "3_3") (pintype "passive"))
      (node (ref "9") (pin "4") (pinfunction "4_4") (pintype "passive"))
      (node (ref "9") (pin "5") (pinfunction "5_5") (pintype "passive"))
      (node (ref "9") (pin "6") (pinfunction "6_6") (pintype "passive"))
      (node (ref "=1") (pin "1") (pinfunction "1_1") (pintype "passive"))
      (node (ref "AMS1") (pin "2") (pinfunction "Vout_2") (pintype "passive"))
      (node (ref "C14") (pin "1") (pinfunction "1_1") (pintype "passive"))
      (node (ref "C15") (pin "1") (pinfunction "1_1") (pintype "passive"))
      (node (ref "C20") (pin "1") (pinfunction "1_1") (pintype "passive"))
      (node (ref "C21") (pin "1") (pinfunction "1_1") (pintype "passive"))
      (node (ref "C22") (pin "1") (pinfunction "1_1") (pintype "passive"))
      (node (ref "C23") (pin "1") (pinfunction "1_1") (pintype "passive"))
      (node (ref "C24") (pin "1") (pinfunction "1_1") (pintype "passive"))
      (node (ref "C25") (pin "1") (pinfunction "1_1") (pintype "passive"))
      (node (ref "C26") (pin "1") (pinfunction "1_1") (pintype "passive"))
      (node (ref "C27") (pin "1") (pinfunction "1_1") (pintype "passive"))
      (node (ref "C28") (pin "1") (pinfunction "1_1") (pintype "passive"))
      (node (ref "C29") (pin "1") (pinfunction "1_1") (pintype "passive"))
      (node (ref "C4") (pin "2") (pinfunction "2_2") (pintype "passive"))
      (node (ref "C5") (pin "2") (pinfunction "2_2") (pintype "passive"))
      (node (ref "D3") (pin "1") (pinfunction "A_1") (pintype "passive"))
      (node (ref "G C D V") (pin "1") (pinfunction "1_1") (pintype "passive"))
      (node (ref "IC2") (pin "8") (pinfunction "VCC_8") (pintype "passive"))
      (node (ref "IC3") (pin "8") (pinfunction "VCC_8") (pintype "power_in"))
      (node (ref "J1") (pin "4") (pinfunction "VDD_4") (pintype "passive"))
      (node (ref "L1") (pin "1") (pinfunction "1_1") (pintype "passive"))
      (node (ref "OLED") (pin "2") (pinfunction "2_2") (pintype "passive"))
      (node (ref "OV2640") (pin "1") (pinfunction "3.3V_1") (pintype "passive"))
      (node (ref "R T G V") (pin "1") (pinfunction "1_1") (pintype "passive"))
      (node (ref "R1") (pin "1") (pinfunction "1_1") (pintype "passive"))
      (node (ref "R10") (pin "2") (pinfunction "2_2") (pintype "passive"))
      (node (ref "R11") (pin "2") (pinfunction "2_2") (pintype "passive"))
      (node (ref "R12") (pin "2") (pinfunction "2_2") (pintype "passive"))
      (node (ref "R14") (pin "1") (pinfunction "1_1") (pintype "passive"))
      (node (ref "R15") (pin "1") (pinfunction "1_1") (pintype "passive"))
      (node (ref "R16") (pin "1") (pinfunction "1_1") (pintype "passive"))
      (node (ref "R17") (pin "1") (pinfunction "1_1") (pintype "passive"))
      (node (ref "R18") (pin "2") (pinfunction "2_2") (pintype "passive"))
      (node (ref "R2") (pin "2") (pinfunction "2_2") (pintype "passive"))
      (node (ref "R3") (pin "5") (pinfunction "5_5") (pintype "passive"))
      (node (ref "R3") (pin "6") (pinfunction "6_6") (pintype "passive"))
      (node (ref "R3") (pin "7") (pinfunction "7_7") (pintype "passive"))
      (node (ref "R3") (pin "8") (pinfunction "8_8") (pintype "passive"))
      (node (ref "R4") (pin "2") (pinfunction "2_2") (pintype "passive"))
      (node (ref "R7") (pin "1") (pinfunction "1_1") (pintype "passive"))
      (node (ref "SW3") (pin "2") (pinfunction "2_2") (pintype "passive"))
      (node (ref "U1") (pin "12") (pinfunction "VCC1_12") (pintype "power_in"))
      (node (ref "U1") (pin "37") (pinfunction "VCC2_37") (pintype "power_in"))
    )
    (net (code "90") (name "5V_USB") (class "Default")
      (node (ref "F1") (pin "1") (pinfunction "1_1") (pintype "passive"))
      (node (ref "R5") (pin "2") (pinfunction "2_2") (pintype "passive"))
      (node (ref "USB1") (pin "A4") (pinfunction "VBUS_A4") (pintype "passive"))
      (node (ref "USB1") (pin "A9") (pinfunction "VBUS_A9") (pintype "passive"))
      (node (ref "USB1") (pin "B4") (pinfunction "VBUS_B4") (pintype "passive"))
      (node (ref "USB1") (pin "B9") (pinfunction "VBUS_B9") (pintype "passive"))
    )
    (net (code "91") (name "GND") (class "Default")
      (node (ref "1") (pin "10") (pinfunction "VSS_10") (pintype "passive"))
      (node (ref "1") (pin "19") (pinfunction "VSSA_19") (pintype "passive"))
      (node (ref "1") (pin "26") (pinfunction "VSS_26") (pintype "passive"))
      (node (ref "1") (pin "49") (pinfunction "VSS_49") (pintype "passive"))
      (node (ref "1") (pin "74") (pinfunction "VSS_74") (pintype "passive"))
      (node (ref "1") (pin "99") (pinfunction "VSS_99") (pintype "passive"))
      (node (ref "8") (pin "1") (pinfunction "1_1") (pintype "passive"))
      (node (ref "8") (pin "16") (pinfunction "16_16") (pintype "passive"))
      (node (ref "8") (pin "2") (pinfunction "2_2") (pintype "passive"))
      (node (ref "8") (pin "33") (pinfunction "33_33") (pintype "passive"))
      (node (ref "8") (pin "34") (pinfunction "34_34") (pintype "passive"))
      (node (ref "8") (pin "35") (pinfunction "35_35") (pintype "passive"))
      (node (ref "8") (pin "36") (pinfunction "36_36") (pintype "passive"))
      (node (ref "9") (pin "10") (pinfunction "10_10") (pintype "passive"))
      (node (ref "9") (pin "11") (pinfunction "11_11") (pintype "passive"))
      (node (ref "9") (pin "12") (pinfunction "12_12") (pintype "passive"))
      (node (ref "9") (pin "29") (pinfunction "29_29") (pintype "passive"))
      (node (ref "9") (pin "37") (pinfunction "37_37") (pintype "passive"))
      (node (ref "9") (pin "38") (pinfunction "38_38") (pintype "passive"))
      (node (ref "9") (pin "7") (pinfunction "7_7") (pintype "passive"))
      (node (ref "9") (pin "8") (pinfunction "8_8") (pintype "passive"))
      (node (ref "9") (pin "9") (pinfunction "9_9") (pintype "passive"))
      (node (ref "=0") (pin "2") (pinfunction "2_2") (pintype "passive"))
      (node (ref "AMS1") (pin "1") (pinfunction "GND_1") (pintype "passive"))
      (node (ref "C1") (pin "1") (pinfunction "1_1") (pintype "passive"))
      (node (ref "C10") (pin "1") (pinfunction "1_1") (pintype "passive"))
      (node (ref "C11") (pin "1") (pinfunction "1_1") (pintype "passive"))
      (node (ref "C12") (pin "1") (pinfunction "1_1") (pintype "passive"))
      (node (ref "C13") (pin "1") (pinfunction "1_1") (pintype "passive"))
      (node (ref "C14") (pin "2") (pinfunction "2_2") (pintype "passive"))
      (node (ref "C15") (pin "2") (pinfunction "2_2") (pintype "passive"))
      (node (ref "C2") (pin "1") (pinfunction "1_1") (pintype "passive"))
      (node (ref "C20") (pin "2") (pinfunction "2_2") (pintype "passive"))
      (node (ref "C21") (pin "2") (pinfunction "2_2") (pintype "passive"))
      (node (ref "C22") (pin "2") (pinfunction "2_2") (pintype "passive"))
      (node (ref "C23") (pin "2") (pinfunction "2_2") (pintype "passive"))
      (node (ref "C24") (pin "2") (pinfunction "2_2") (pintype "passive"))
      (node (ref "C25") (pin "2") (pinfunction "2_2") (pintype "passive"))
      (node (ref "C26") (pin "2") (pinfunction "2_2") (pintype "passive"))
      (node (ref "C27") (pin "2") (pinfunction "2_2") (pintype "passive"))
      (node (ref "C28") (pin "2") (pinfunction "2_2") (pintype "passive"))
      (node (ref "C29") (pin "2") (pinfunction "2_2") (pintype "passive"))
      (node (ref "C3") (pin "1") (pinfunction "1_1") (pintype "passive"))
      (node (ref "C30") (pin "2") (pinfunction "2_2") (pintype "passive"))
      (node (ref "C4") (pin "1") (pinfunction "1_1") (pintype "passive"))
      (node (ref "C5") (pin "1") (pinfunction "1_1") (pintype "passive"))
      (node (ref "C6") (pin "2") (pinfunction "2_2") (pintype "passive"))
      (node (ref "C7") (pin "2") (pinfunction "2_2") (pintype "passive"))
      (node (ref "C8") (pin "2") (pinfunction "2_2") (pintype "passive"))
      (node (ref "C9") (pin "1") (pinfunction "1_1") (pintype "passive"))
      (node (ref "CR1") (pin "2") (pinfunction "DC-_2") (pintype "passive"))
      (node (ref "D1") (pin "2") (pinfunction "CATHODE_2") (pintype "passive"))
      (node (ref "G C D V") (pin "4") (pinfunction "4_4") (pintype "passive"))
      (node (ref "IC1") (pin "2") (pinfunction "GND_2") (pintype "passive"))
      (node (ref "IC1") (pin "8") (pinfunction "S_8") (pintype "passive"))
      (node (ref "IC2") (pin "4") (pinfunction "GND_4") (pintype "passive"))
      (node (ref "IC3") (pin "1") (pinfunction "A0_1") (pintype "input"))
      (node (ref "IC3") (pin "2") (pinfunction "A1_2") (pintype "input"))
      (node (ref "IC3") (pin "3") (pinfunction "A2_3") (pintype "input"))
      (node (ref "IC3") (pin "4") (pinfunction "GND_4") (pintype "passive"))
      (node (ref "IC3") (pin "7") (pinfunction "WP_7") (pintype "passive"))
      (node (ref "J1") (pin "10") (pinfunction "GND_10") (pintype "passive"))
      (node (ref "J1") (pin "6") (pinfunction "VSS_6") (pintype "passive"))
      (node (ref "OLED") (pin "1") (pinfunction "1_1") (pintype "passive"))
      (node (ref "OV2640") (pin "2") (pinfunction "GND_2") (pintype "passive"))
      (node (ref "R T G V") (pin "2") (pinfunction "2_2") (pintype "passive"))
      (node (ref "RST1") (pin "1") (pinfunction "1_1") (pintype "passive"))
      (node (ref "SW1") (pin "2") (pinfunction "2_2") (pintype "passive"))
      (node (ref "SW2") (pin "2") (pinfunction "2_2") (pintype "passive"))
      (node (ref "U1") (pin "13") (pinfunction "VSS1_13") (pintype "passive"))
      (node (ref "U1") (pin "36") (pinfunction "VSS2_36") (pintype "passive"))
      (node (ref "USB1") (pin "A1") (pinfunction "GND_A1") (pintype "passive"))
      (node (ref "USB1") (pin "A12") (pinfunction "GND_A12") (pintype "passive"))
      (node (ref "USB1") (pin "B1") (pinfunction "GND_B1") (pintype "passive"))
      (node (ref "USB1") (pin "B12") (pinfunction "GND_B12") (pintype "passive"))
      (node (ref "X1") (pin "2") (pinfunction "2_2") (pintype "passive"))
      (node (ref "X1") (pin "4") (pinfunction "4_4") (pintype "passive"))
      (node (ref "Z1") (pin "3") (pintype "passive"))
    )
    (net (code "92") (name "Net-(1-VCAP1)") (class "Default")
      (node (ref "1") (pin "48") (pinfunction "VCAP1_48") (pintype "passive"))
      (node (ref "C9") (pin "2") (pinfunction "2_2") (pintype "passive"))
    )
    (net (code "93") (name "Net-(1-VCAP2)") (class "Default")
      (node (ref "1") (pin "73") (pinfunction "VCAP2_73") (pintype "passive"))
      (node (ref "C6") (pin "1") (pinfunction "1_1") (pintype "passive"))
    )
    (net (code "94") (name "Net-(1-VDDA)") (class "Default")
      (node (ref "1") (pin "20") (pinfunction "VREF+_20") (pintype "passive"))
      (node (ref "1") (pin "21") (pinfunction "VDDA_21") (pintype "passive"))
      (node (ref "C7") (pin "1") (pinfunction "1_1") (pintype "passive"))
      (node (ref "C8") (pin "1") (pinfunction "1_1") (pintype "passive"))
      (node (ref "L1") (pin "2") (pinfunction "2_2") (pintype "passive"))
    )
    (net (code "95") (name "Net-(CR1-DC+)") (class "Default")
      (node (ref "CR1") (pin "1") (pinfunction "DC+_1") (pintype "passive"))
      (node (ref "D2") (pin "1") (pinfunction "A_1") (pintype "passive"))
    )
    (net (code "96") (name "Net-(D1-ANODE)") (class "Default")
      (node (ref "D1") (pin "1") (pinfunction "ANODE_1") (pintype "passive"))
      (node (ref "R2") (pin "1") (pinfunction "1_1") (pintype "passive"))
    )
    (net (code "97") (name "Net-(IC1-CANH)") (class "Default")
      (node (ref "CAN") (pin "1") (pinfunction "1_1") (pintype "passive"))
      (node (ref "IC1") (pin "7") (pinfunction "CANH_7") (pintype "passive"))
      (node (ref "R13") (pin "2") (pinfunction "2_2") (pintype "passive"))
      (node (ref "Z1") (pin "2") (pintype "passive"))
    )
    (net (code "98") (name "Net-(IC1-CANL)") (class "Default")
      (node (ref "CAN") (pin "2") (pinfunction "2_2") (pintype "passive"))
      (node (ref "IC1") (pin "6") (pinfunction "CANL_6") (pintype "passive"))
      (node (ref "R13") (pin "1") (pinfunction "1_1") (pintype "passive"))
      (node (ref "Z1") (pin "1") (pintype "passive"))
    )
    (net (code "99") (name "Net-(J1-K)") (class "Default")
      (node (ref "J1") (pin "9") (pinfunction "K_9") (pintype "passive"))
      (node (ref "R7") (pin "2") (pinfunction "2_2") (pintype "passive"))
      (node (ref "R9") (pin "1") (pinfunction "1_1") (pintype "passive"))
    )
    (net (code "100") (name "Net-(RGB1-BULE_A)") (class "Default")
      (node (ref "R12") (pin "1") (pinfunction "1_1") (pintype "passive"))
      (node (ref "RGB1") (pin "2") (pinfunction "BULE_A_2") (pintype "passive"))
    )
    (net (code "101") (name "Net-(RGB1-GREEN_A)") (class "Default")
      (node (ref "R10") (pin "1") (pinfunction "1_1") (pintype "passive"))
      (node (ref "RGB1") (pin "6") (pinfunction "GREEN_A_6") (pintype "passive"))
    )
    (net (code "102") (name "Net-(RGB1-RED_A)") (class "Default")
      (node (ref "R11") (pin "1") (pinfunction "1_1") (pintype "passive"))
      (node (ref "RGB1") (pin "4") (pinfunction "RED_A_4") (pintype "passive"))
    )
    (net (code "103") (name "Net-(U1-~{WP})") (class "Default")
      (node (ref "R16") (pin "2") (pinfunction "2_2") (pintype "passive"))
      (node (ref "U1") (pin "19") (pinfunction "~{WP}_19") (pintype "input"))
    )
    (net (code "104") (name "unconnected-(IC1-VREF-Pad5)") (class "Default")
      (node (ref "IC1") (pin "5") (pinfunction "VREF_5") (pintype "passive+no_connect"))
    )
    (net (code "105") (name "unconnected-(OV2640-XCLK-Pad17)") (class "Default")
      (node (ref "OV2640") (pin "17") (pinfunction "XCLK_17") (pintype "passive+no_connect"))
    )
    (net (code "106") (name "unconnected-(U1-NC1-Pad1)") (class "Default")
      (node (ref "U1") (pin "1") (pinfunction "NC1_1") (pintype "passive+no_connect"))
    )
    (net (code "107") (name "unconnected-(U1-NC2-Pad2)") (class "Default")
      (node (ref "U1") (pin "2") (pinfunction "NC2_2") (pintype "passive+no_connect"))
    )
    (net (code "108") (name "unconnected-(U1-NC3-Pad3)") (class "Default")
      (node (ref "U1") (pin "3") (pinfunction "NC3_3") (pintype "passive+no_connect"))
    )
    (net (code "109") (name "unconnected-(U1-NC4-Pad4)") (class "Default")
      (node (ref "U1") (pin "4") (pinfunction "NC4_4") (pintype "passive+no_connect"))
    )
    (net (code "110") (name "unconnected-(U1-NC5-Pad5)") (class "Default")
      (node (ref "U1") (pin "5") (pinfunction "NC5_5") (pintype "passive+no_connect"))
    )
    (net (code "111") (name "unconnected-(U1-NC6-Pad6)") (class "Default")
      (node (ref "U1") (pin "6") (pinfunction "NC6_6") (pintype "passive+no_connect"))
    )
    (net (code "112") (name "unconnected-(U1-NC10-Pad10)") (class "Default")
      (node (ref "U1") (pin "10") (pinfunction "NC10_10") (pintype "passive+no_connect"))
    )
    (net (code "113") (name "unconnected-(U1-NC11-Pad11)") (class "Default")
      (node (ref "U1") (pin "11") (pinfunction "NC11_11") (pintype "passive+no_connect"))
    )
    (net (code "114") (name "unconnected-(U1-NC14-Pad14)") (class "Default")
      (node (ref "U1") (pin "14") (pinfunction "NC14_14") (pintype "passive+no_connect"))
    )
    (net (code "115") (name "unconnected-(U1-NC15-Pad15)") (class "Default")
      (node (ref "U1") (pin "15") (pinfunction "NC15_15") (pintype "passive+no_connect"))
    )
    (net (code "116") (name "unconnected-(U1-NC20-Pad20)") (class "Default")
      (node (ref "U1") (pin "20") (pinfunction "NC20_20") (pintype "passive+no_connect"))
    )
    (net (code "117") (name "unconnected-(U1-NC21-Pad21)") (class "Default")
      (node (ref "U1") (pin "21") (pinfunction "NC21_21") (pintype "passive+no_connect"))
    )
    (net (code "118") (name "unconnected-(U1-NC22-Pad22)") (class "Default")
      (node (ref "U1") (pin "22") (pinfunction "NC22_22") (pintype "passive+no_connect"))
    )
    (net (code "119") (name "unconnected-(U1-NC23-Pad23)") (class "Default")
      (node (ref "U1") (pin "23") (pinfunction "NC23_23") (pintype "passive+no_connect"))
    )
    (net (code "120") (name "unconnected-(U1-NC24-Pad24)") (class "Default")
      (node (ref "U1") (pin "24") (pinfunction "NC24_24") (pintype "passive+no_connect"))
    )
    (net (code "121") (name "unconnected-(U1-NC25-Pad25)") (class "Default")
      (node (ref "U1") (pin "25") (pinfunction "NC25_25") (pintype "passive+no_connect"))
    )
    (net (code "122") (name "unconnected-(U1-NC26-Pad26)") (class "Default")
      (node (ref "U1") (pin "26") (pinfunction "NC26_26") (pintype "passive+no_connect"))
    )
    (net (code "123") (name "unconnected-(U1-NC27-Pad27)") (class "Default")
      (node (ref "U1") (pin "27") (pinfunction "NC27_27") (pintype "passive+no_connect"))
    )
    (net (code "124") (name "unconnected-(U1-NC28-Pad28)") (class "Default")
      (node (ref "U1") (pin "28") (pinfunction "NC28_28") (pintype "passive+no_connect"))
    )
    (net (code "125") (name "unconnected-(U1-NC33-Pad33)") (class "Default")
      (node (ref "U1") (pin "33") (pinfunction "NC33_33") (pintype "passive+no_connect"))
    )
    (net (code "126") (name "unconnected-(U1-NC34-Pad34)") (class "Default")
      (node (ref "U1") (pin "34") (pinfunction "NC34_34") (pintype "passive+no_connect"))
    )
    (net (code "127") (name "unconnected-(U1-NC35-Pad35)") (class "Default")
      (node (ref "U1") (pin "35") (pinfunction "NC35_35") (pintype "passive+no_connect"))
    )
    (net (code "128") (name "unconnected-(U1-NC38-Pad38)") (class "Default")
      (node (ref "U1") (pin "38") (pinfunction "NC38_38") (pintype "passive+no_connect"))
    )
    (net (code "129") (name "unconnected-(U1-NC39-Pad39)") (class "Default")
      (node (ref "U1") (pin "39") (pinfunction "NC39_39") (pintype "passive+no_connect"))
    )
    (net (code "130") (name "unconnected-(U1-NC40-Pad40)") (class "Default")
      (node (ref "U1") (pin "40") (pinfunction "NC40_40") (pintype "passive+no_connect"))
    )
    (net (code "131") (name "unconnected-(U1-NC45-Pad45)") (class "Default")
      (node (ref "U1") (pin "45") (pinfunction "NC45_45") (pintype "passive+no_connect"))
    )
    (net (code "132") (name "unconnected-(U1-NC46-Pad46)") (class "Default")
      (node (ref "U1") (pin "46") (pinfunction "NC46_46") (pintype "passive+no_connect"))
    )
    (net (code "133") (name "unconnected-(U1-NC47-Pad47)") (class "Default")
      (node (ref "U1") (pin "47") (pinfunction "NC47_47") (pintype "passive+no_connect"))
    )
    (net (code "134") (name "unconnected-(U1-NC48-Pad48)") (class "Default")
      (node (ref "U1") (pin "48") (pinfunction "NC48_48") (pintype "passive+no_connect"))
    )
    (net (code "135") (name "unconnected-(USB1-CC1-PadA5)") (class "Default")
      (node (ref "USB1") (pin "A5") (pinfunction "CC1_A5") (pintype "passive+no_connect"))
    )
    (net (code "136") (name "unconnected-(USB1-CC2-PadB5)") (class "Default")
      (node (ref "USB1") (pin "B5") (pinfunction "CC2_B5") (pintype "passive+no_connect"))
    )
    (net (code "137") (name "unconnected-(USB1-SBU1-PadA8)") (class "Default")
      (node (ref "USB1") (pin "A8") (pinfunction "SBU1_A8") (pintype "passive+no_connect"))
    )
    (net (code "138") (name "unconnected-(USB1-SBU2-PadB8)") (class "Default")
      (node (ref "USB1") (pin "B8") (pinfunction "SBU2_B8") (pintype "passive+no_connect"))
    )
    (net (code "139") (name "unconnected-(USB1-SSRXn1-PadB10)") (class "Default")
      (node (ref "USB1") (pin "B10") (pinfunction "SSRXn1_B10") (pintype "passive+no_connect"))
    )
    (net (code "140") (name "unconnected-(USB1-SSRXn2-PadA10)") (class "Default")
      (node (ref "USB1") (pin "A10") (pinfunction "SSRXn2_A10") (pintype "passive+no_connect"))
    )
    (net (code "141") (name "unconnected-(USB1-SSRXp1-PadB11)") (class "Default")
      (node (ref "USB1") (pin "B11") (pinfunction "SSRXp1_B11") (pintype "passive+no_connect"))
    )
    (net (code "142") (name "unconnected-(USB1-SSRXp2-PadA11)") (class "Default")
      (node (ref "USB1") (pin "A11") (pinfunction "SSRXp2_A11") (pintype "passive+no_connect"))
    )
    (net (code "143") (name "unconnected-(USB1-SSTXn1-PadA3)") (class "Default")
      (node (ref "USB1") (pin "A3") (pinfunction "SSTXn1_A3") (pintype "passive+no_connect"))
    )
    (net (code "144") (name "unconnected-(USB1-SSTXn2-PadB3)") (class "Default")
      (node (ref "USB1") (pin "B3") (pinfunction "SSTXn2_B3") (pintype "passive+no_connect"))
    )
    (net (code "145") (name "unconnected-(USB1-SSTXp1-PadA2)") (class "Default")
      (node (ref "USB1") (pin "A2") (pinfunction "SSTXp1_A2") (pintype "passive+no_connect"))
    )
    (net (code "146") (name "unconnected-(USB1-SSTXp2-PadB2)") (class "Default")
      (node (ref "USB1") (pin "B2") (pinfunction "SSTXp2_B2") (pintype "passive+no_connect"))
    )
  )
)
